# TCS3471-3V-v1_0.net
KiCad netlist of a schematic drawn in EAGLE
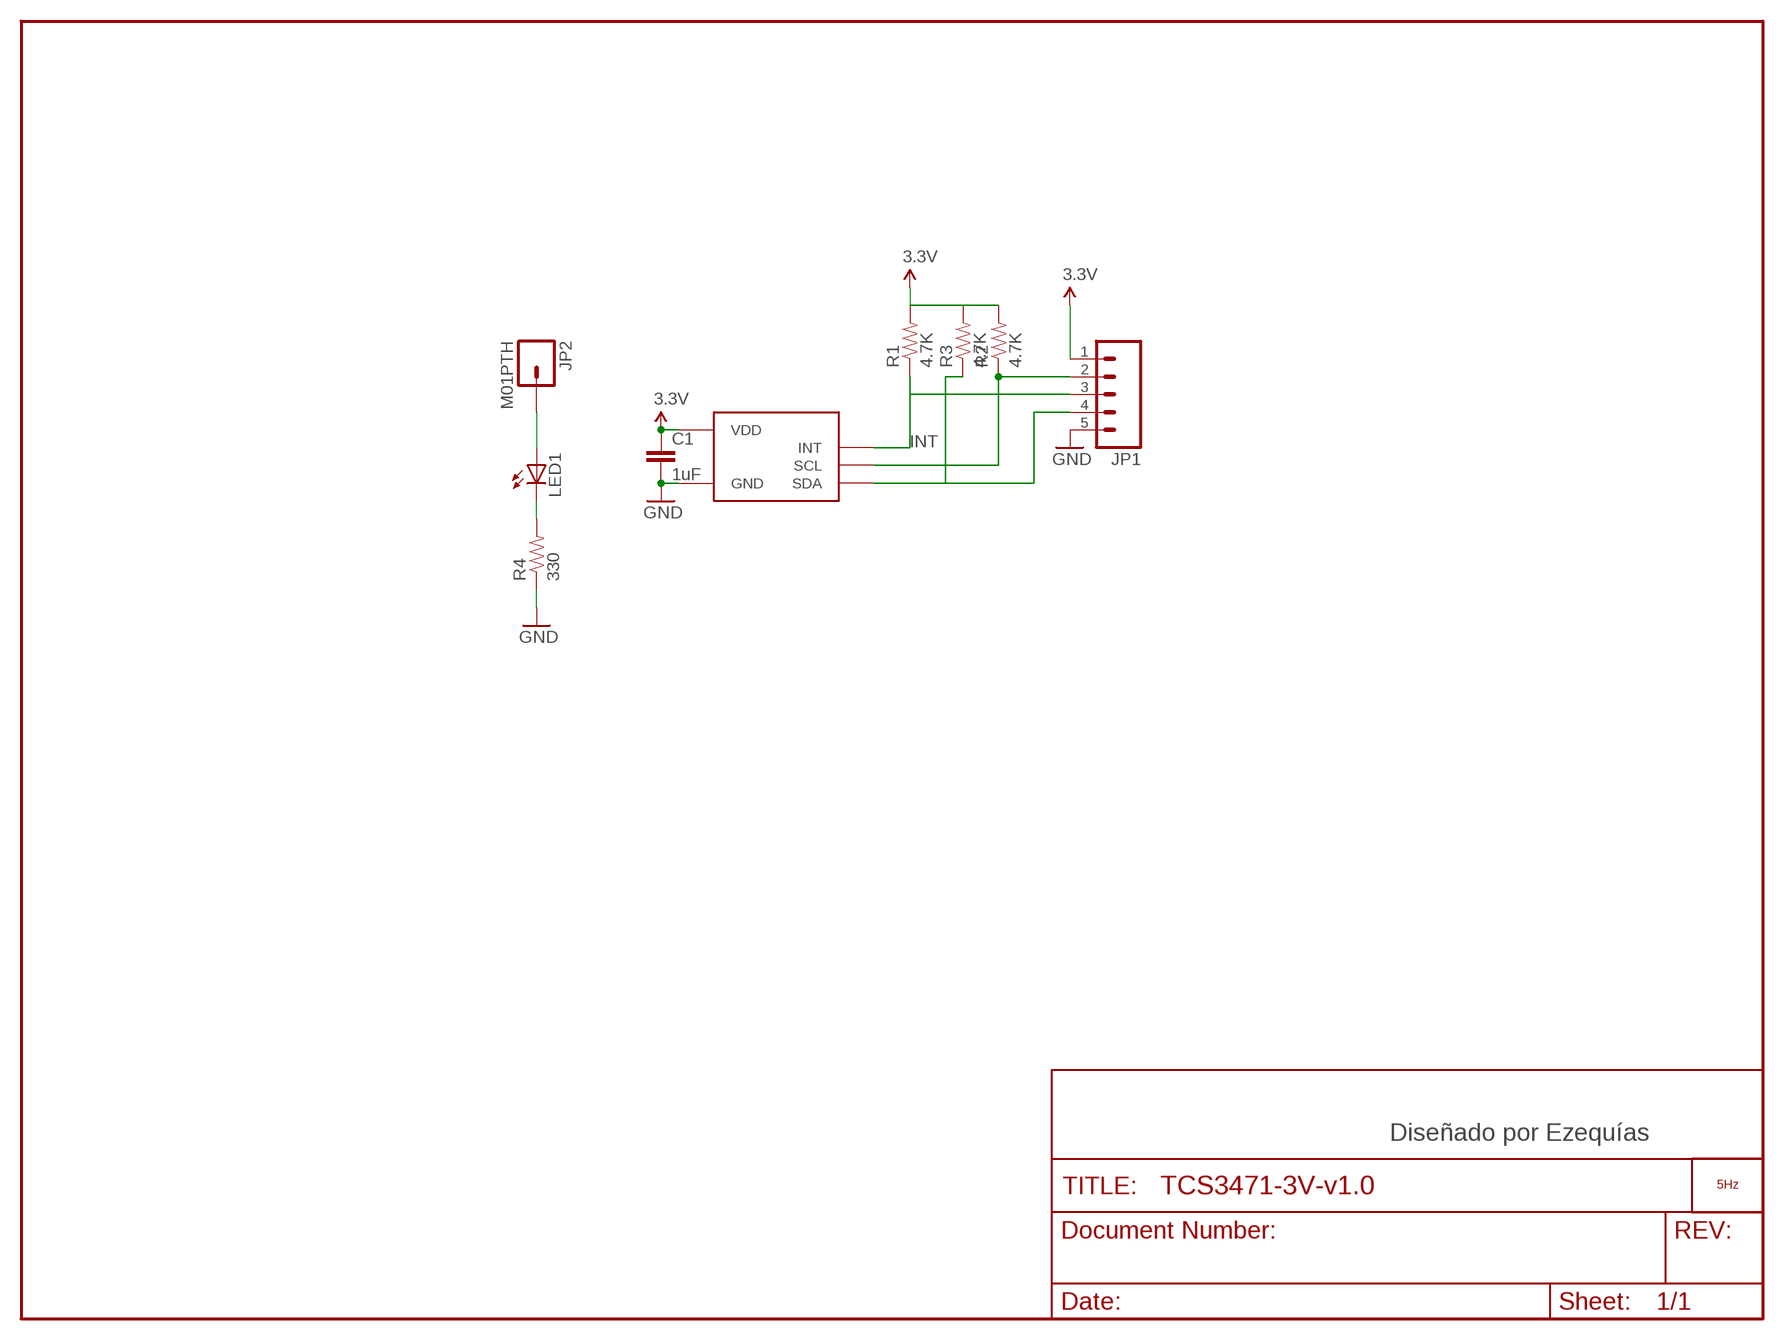
[diagram p0: schematic, sheet 1]

(export (version "E")
  (design (tool "Eeschema 10.0.6"))
  (components
    (comp (ref "C1")
      (value "1uF")
      (footprint "eagle-import:0603-CAP")
      (libsource (lib "eagle-import") (part "CAP0603-CAP"))
    )
    (comp (ref "JP1")
      (value "M05PTH")
      (footprint "eagle-import:1X05")
      (libsource (lib "eagle-import") (part "M05PTH"))
    )
    (comp (ref "JP2")
      (value "M01PTH")
      (footprint "eagle-import:1X01")
      (libsource (lib "eagle-import") (part "M01PTH"))
    )
    (comp (ref "LED1")
      (value "LED0603")
      (footprint "eagle-import:LED-0603")
      (libsource (lib "eagle-import") (part "LED0603"))
    )
    (comp (ref "LOGO1")
      (value "LOGO_5HZ_H_5MM")
      (footprint "eagle-import:5HZ_LOGO_H_5MM")
      (libsource (lib "eagle-import") (part "LOGO_5HZ_H_5MM"))
    )
    (comp (ref "R1")
      (value "4.7K")
      (footprint "eagle-import:0603-RES")
      (libsource (lib "eagle-import") (part "RESISTOR0603-RES"))
    )
    (comp (ref "R2")
      (value "4.7K")
      (footprint "eagle-import:0603-RES")
      (libsource (lib "eagle-import") (part "RESISTOR0603-RES"))
    )
    (comp (ref "R3")
      (value "4.7K")
      (footprint "eagle-import:0603-RES")
      (libsource (lib "eagle-import") (part "RESISTOR0603-RES"))
    )
    (comp (ref "R4")
      (value "330")
      (footprint "eagle-import:0603-RES")
      (libsource (lib "eagle-import") (part "RESISTOR0603-RES"))
    )
    (comp (ref "U$1")
      (value "TCS3471")
      (footprint "eagle-import:TCS3471")
      (libsource (lib "eagle-import") (part "TCS3471"))
    )
  )
  (nets
    (net (code "1") (name "/INT") (class "Default")
      (node (ref "JP1") (pin "3") (pinfunction "3_3") (pintype "passive"))
      (node (ref "R1") (pin "1") (pinfunction "1_1") (pintype "passive"))
      (node (ref "U$1") (pin "P$5") (pinfunction "INT_P$5") (pintype "bidirectional"))
    )
    (net (code "2") (name "3.3V") (class "Default")
      (node (ref "C1") (pin "1") (pinfunction "1_1") (pintype "passive"))
      (node (ref "JP1") (pin "1") (pinfunction "1_1") (pintype "passive"))
      (node (ref "R1") (pin "2") (pinfunction "2_2") (pintype "passive"))
      (node (ref "R2") (pin "2") (pinfunction "2_2") (pintype "passive"))
      (node (ref "R3") (pin "2") (pinfunction "2_2") (pintype "passive"))
      (node (ref "U$1") (pin "P$1") (pinfunction "VDD_P$1") (pintype "bidirectional"))
    )
    (net (code "3") (name "GND") (class "Default")
      (node (ref "C1") (pin "2") (pinfunction "2_2") (pintype "passive"))
      (node (ref "JP1") (pin "5") (pinfunction "5_5") (pintype "passive"))
      (node (ref "R4") (pin "1") (pinfunction "1_1") (pintype "passive"))
      (node (ref "U$1") (pin "P$3") (pinfunction "GND_P$3") (pintype "bidirectional"))
    )
    (net (code "4") (name "Net-(JP2-Pad1)") (class "Default")
      (node (ref "JP2") (pin "1") (pinfunction "1_1") (pintype "passive"))
      (node (ref "LED1") (pin "A") (pinfunction "A_A") (pintype "passive"))
    )
    (net (code "5") (name "Net-(LED1-PadC)") (class "Default")
      (node (ref "LED1") (pin "C") (pinfunction "C_C") (pintype "passive"))
      (node (ref "R4") (pin "2") (pinfunction "2_2") (pintype "passive"))
    )
    (net (code "6") (name "Net-(U$1-SCL)") (class "Default")
      (node (ref "JP1") (pin "2") (pinfunction "2_2") (pintype "passive"))
      (node (ref "R2") (pin "1") (pinfunction "1_1") (pintype "passive"))
      (node (ref "U$1") (pin "P$2") (pinfunction "SCL_P$2") (pintype "bidirectional"))
    )
    (net (code "7") (name "Net-(U$1-SDA)") (class "Default")
      (node (ref "JP1") (pin "4") (pinfunction "4_4") (pintype "passive"))
      (node (ref "R3") (pin "1") (pinfunction "1_1") (pintype "passive"))
      (node (ref "U$1") (pin "P$6") (pinfunction "SDA_P$6") (pintype "bidirectional"))
    )
  )
)
